# SwirlsV1_2.net
KiCad netlist of a schematic drawn in EAGLE
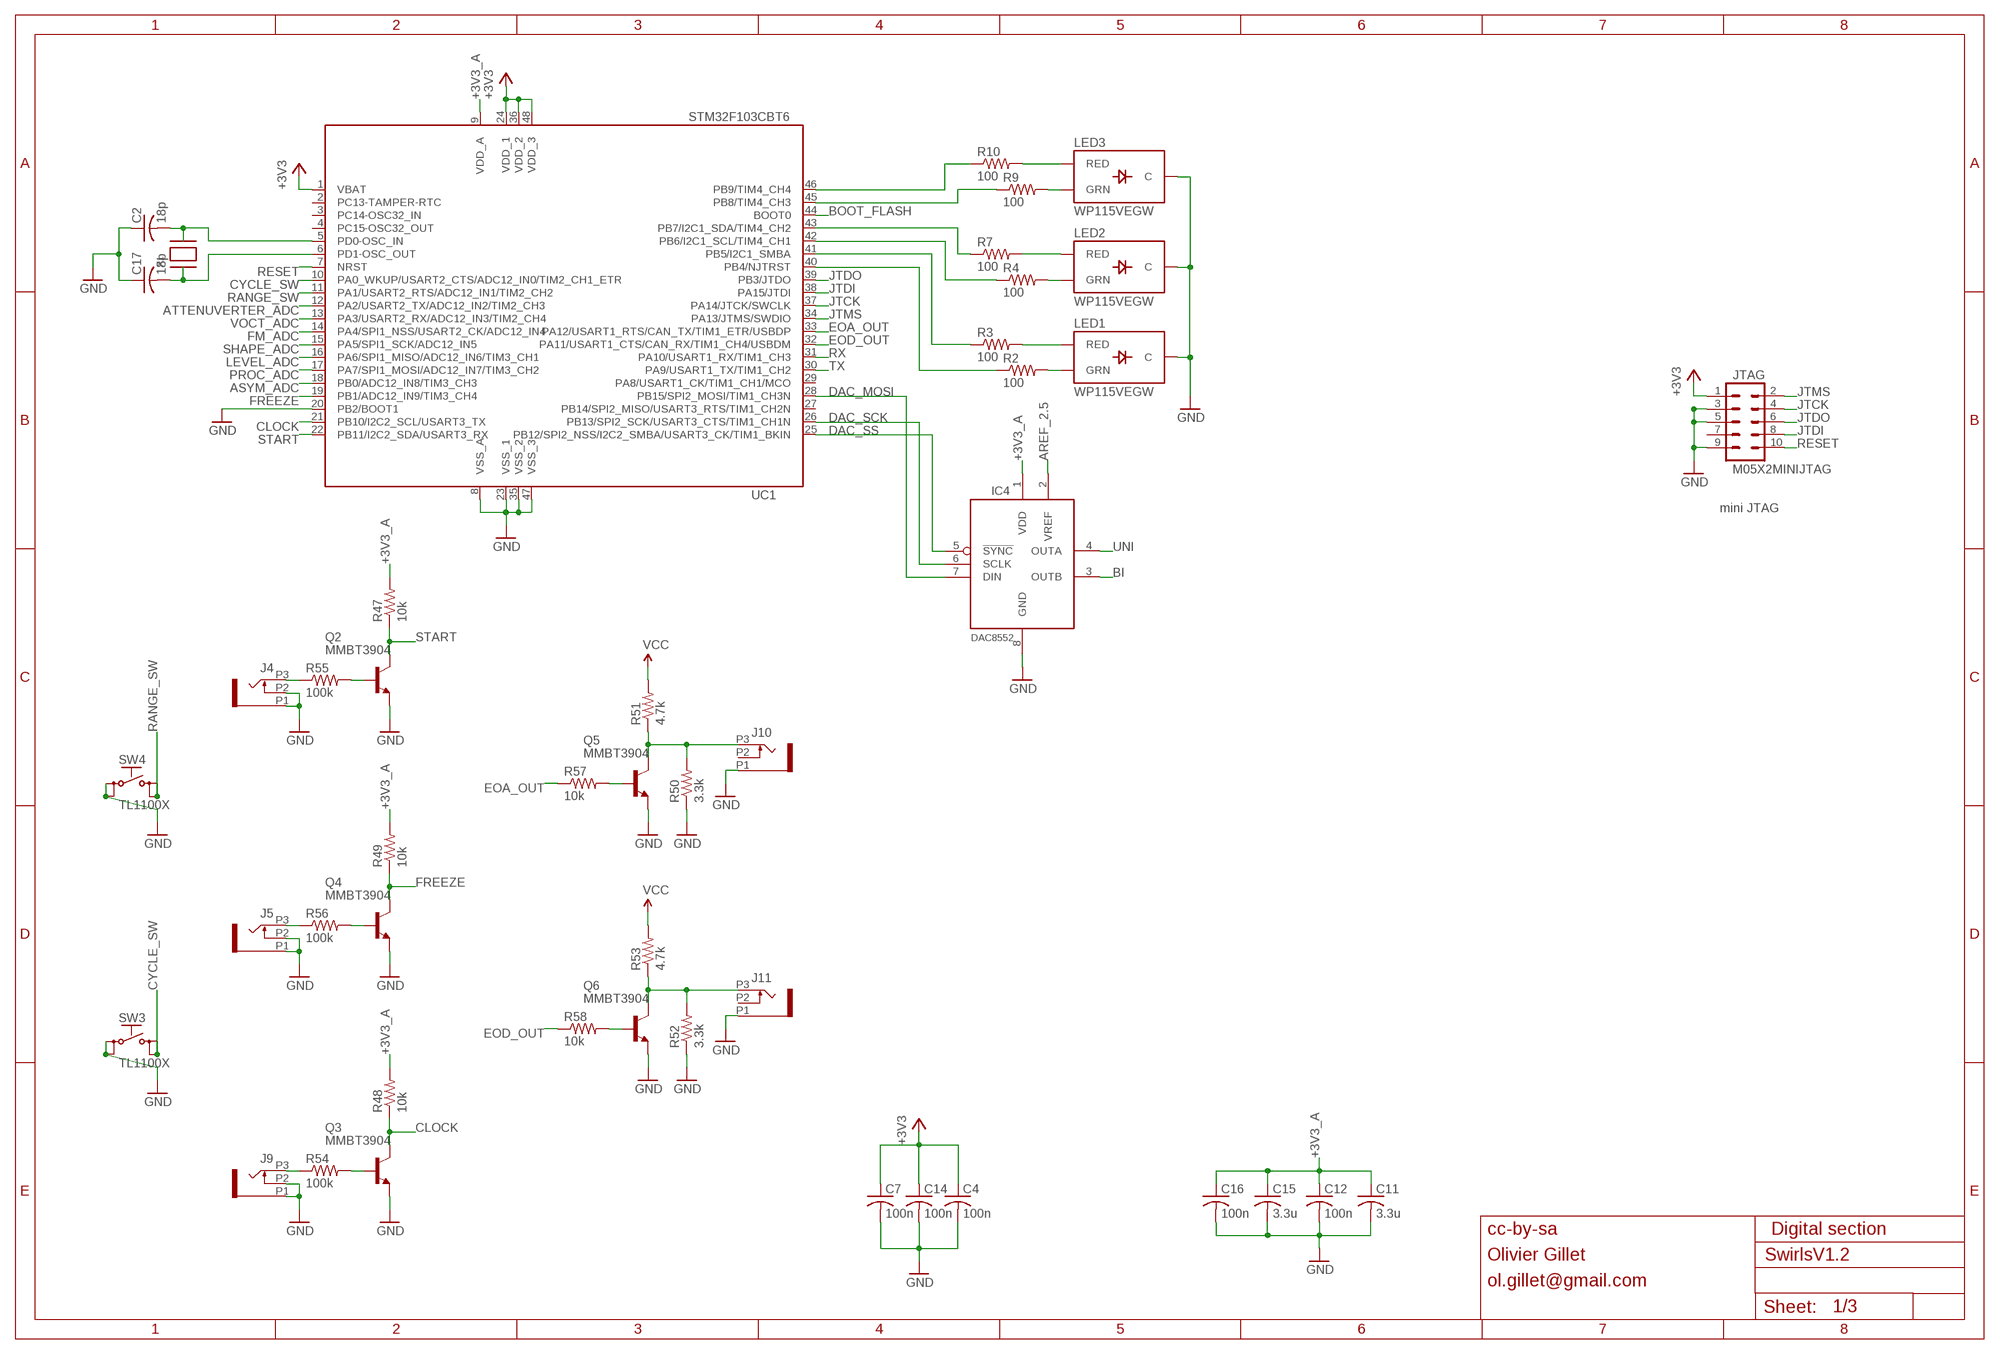
[diagram p0: schematic, sheet 1]
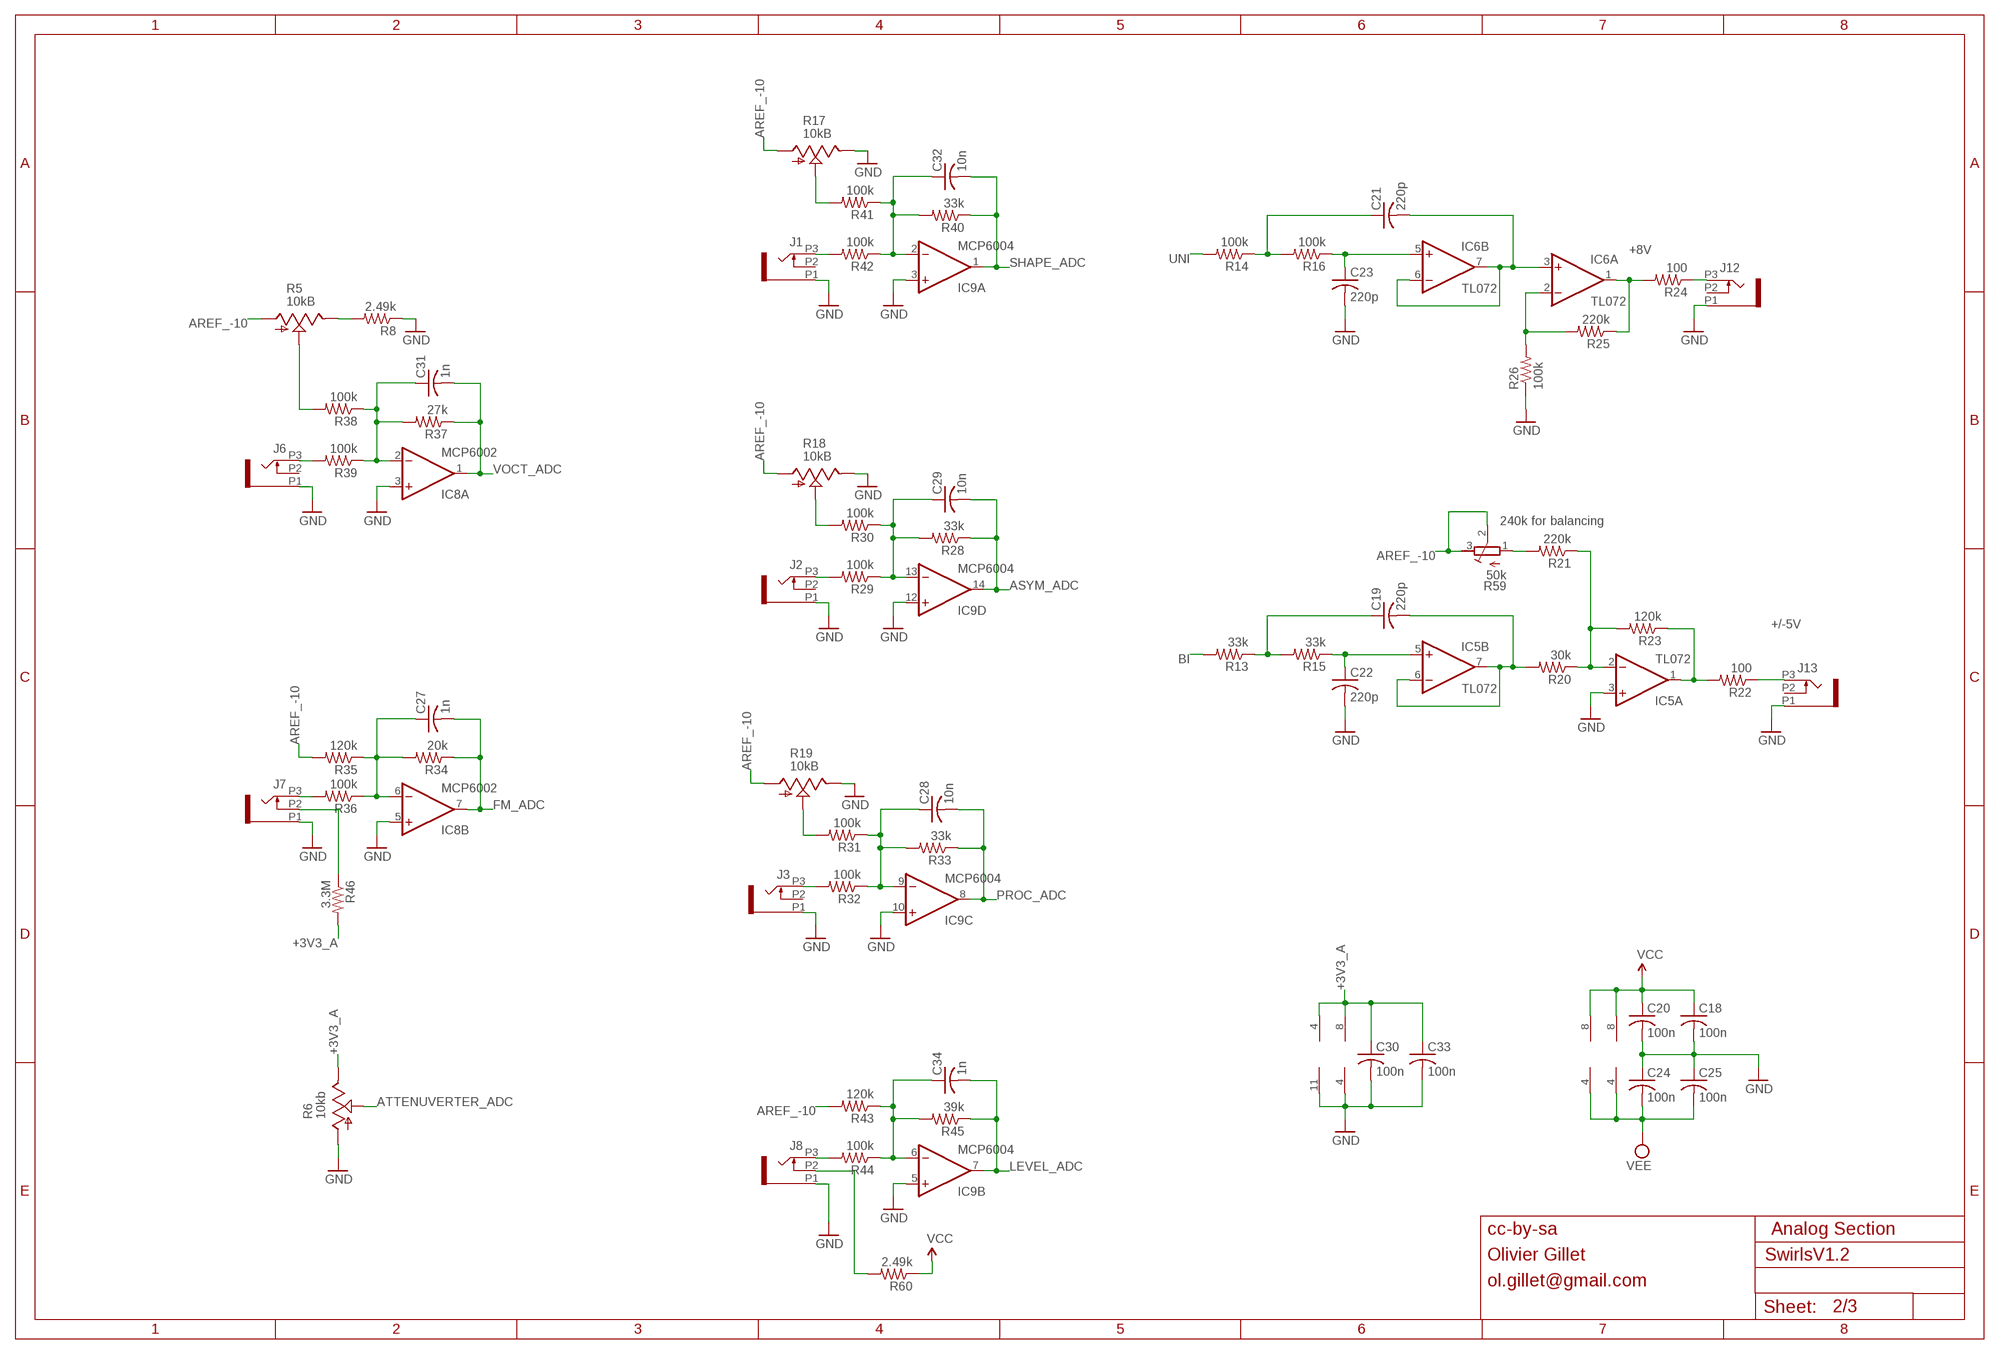
[diagram p1: schematic, sheet 2]
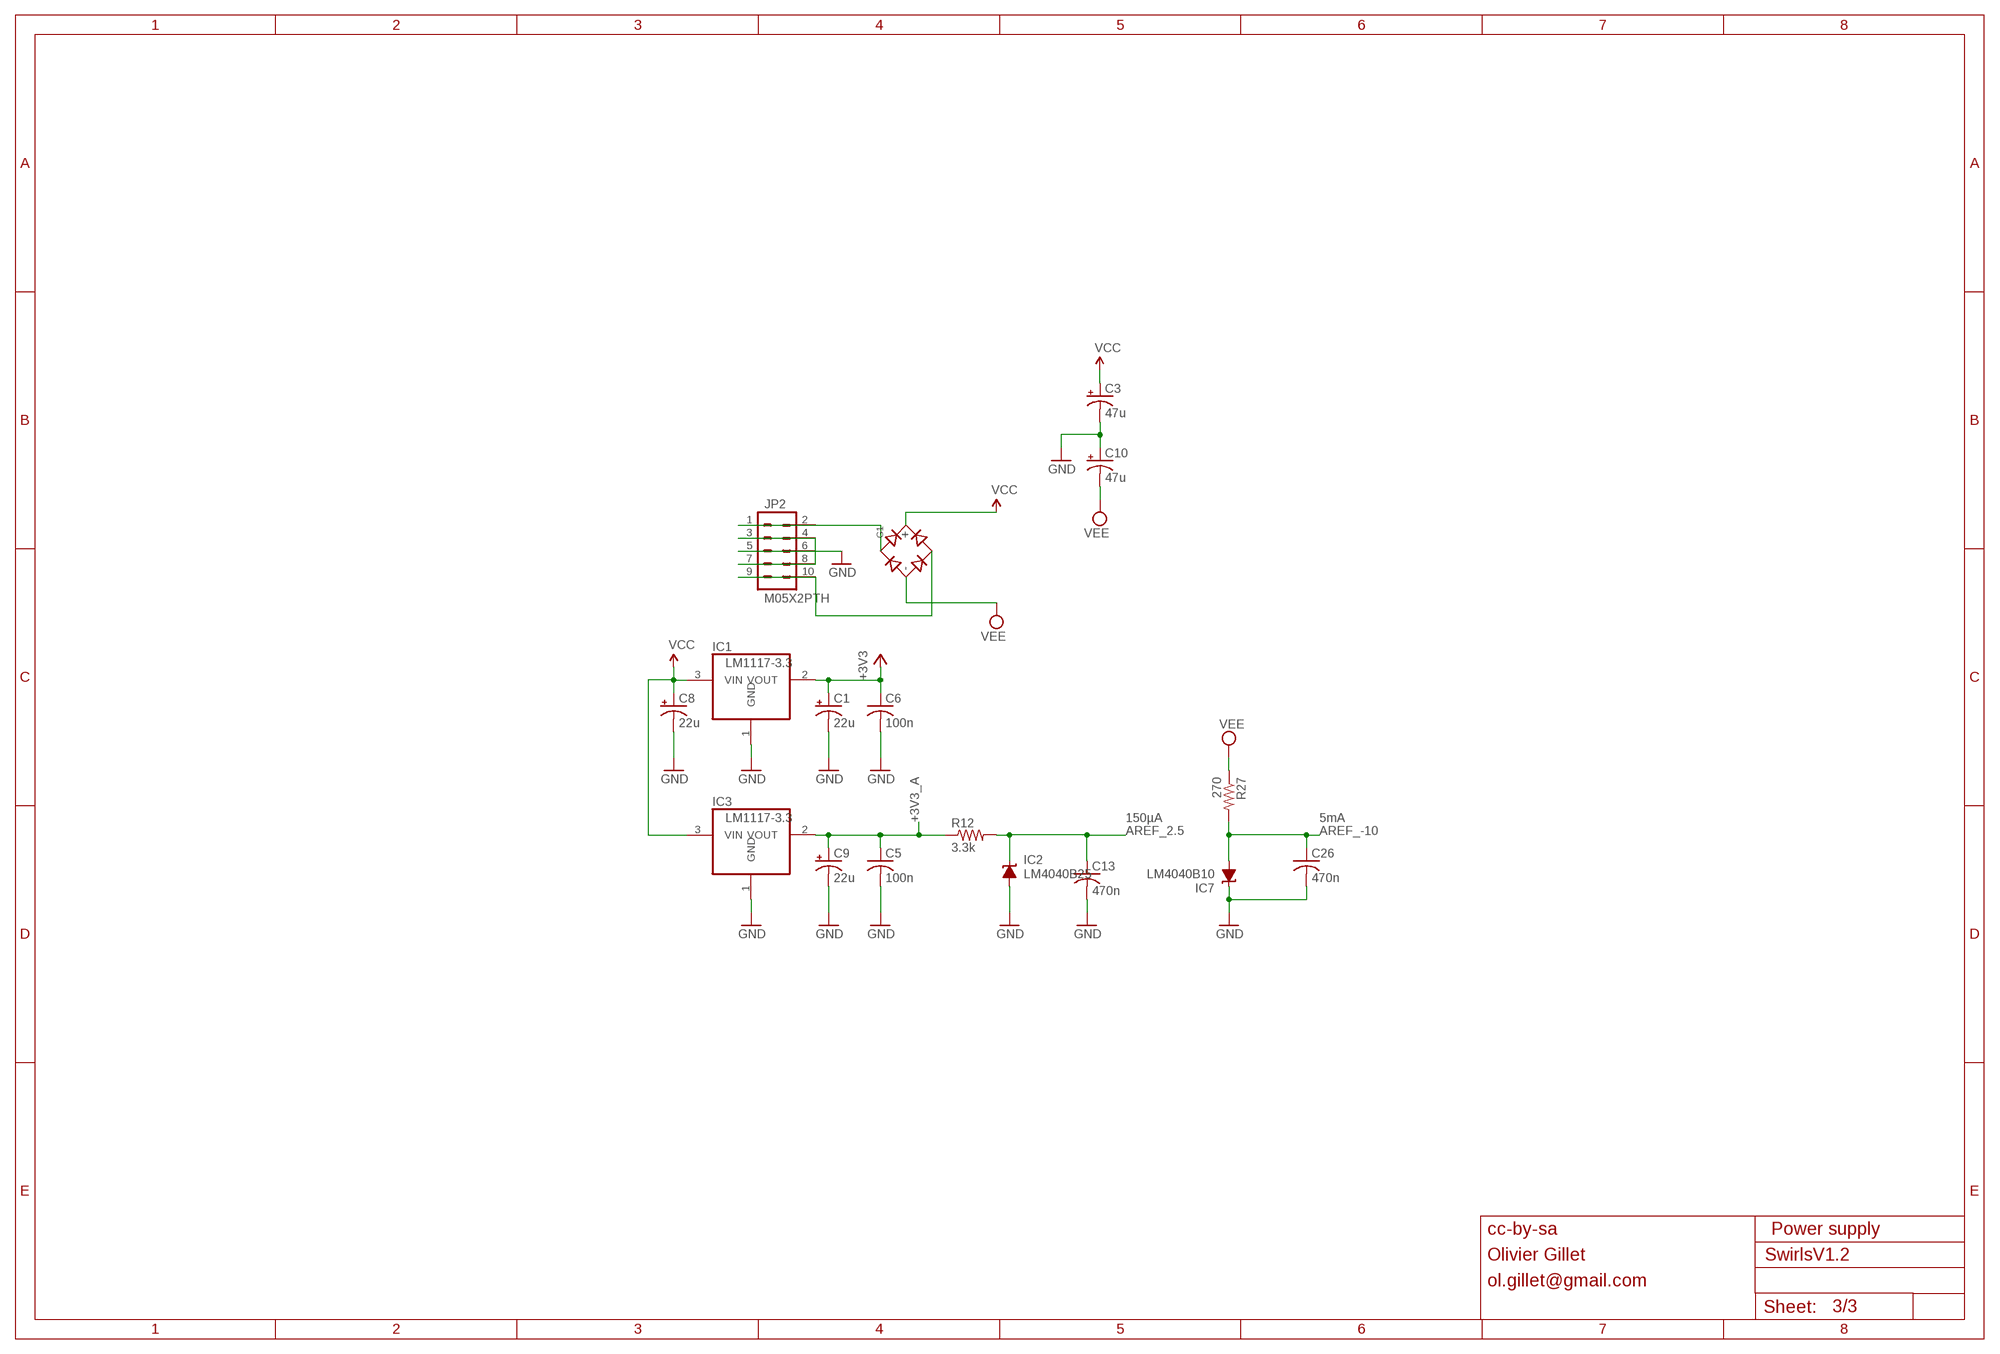
[diagram p2: schematic, sheet 3]

(export (version "E")
  (design (tool "Eeschema 10.0.6"))
  (components
    (comp (ref "C1")
      (value "22u")
      (footprint "eagle-import:PANASONIC_C")
      (libsource (lib "eagle-import") (part "CPOL-USC"))
    )
    (comp (ref "C3")
      (value "47u")
      (footprint "eagle-import:PANASONIC_C")
      (libsource (lib "eagle-import") (part "CPOL-USC"))
    )
    (comp (ref "C5")
      (value "100n")
      (footprint "eagle-import:C0603")
      (libsource (lib "eagle-import") (part "C-USC0603"))
    )
    (comp (ref "C6")
      (value "100n")
      (footprint "eagle-import:C0603")
      (libsource (lib "eagle-import") (part "C-USC0603"))
    )
    (comp (ref "C8")
      (value "22u")
      (footprint "eagle-import:PANASONIC_C")
      (libsource (lib "eagle-import") (part "CPOL-USC"))
    )
    (comp (ref "C9")
      (value "22u")
      (footprint "eagle-import:PANASONIC_C")
      (libsource (lib "eagle-import") (part "CPOL-USC"))
    )
    (comp (ref "C10")
      (value "47u")
      (footprint "eagle-import:PANASONIC_C")
      (libsource (lib "eagle-import") (part "CPOL-USC"))
    )
    (comp (ref "C13")
      (value "470n")
      (footprint "eagle-import:C0603")
      (libsource (lib "eagle-import") (part "C-USC0603"))
    )
    (comp (ref "C26")
      (value "470n")
      (footprint "eagle-import:C0603")
      (libsource (lib "eagle-import") (part "C-USC0603"))
    )
    (comp (ref "G1")
      (value "BRIDGERECTIFIER")
      (footprint "eagle-import:SOIC-4")
      (libsource (lib "eagle-import") (part "BRIDGERECTIFIER"))
    )
    (comp (ref "IC1")
      (value "LM1117-3.3")
      (footprint "eagle-import:SOT223")
      (libsource (lib "eagle-import") (part "REG1117"))
    )
    (comp (ref "IC2")
      (value "LM4040B25")
      (footprint "eagle-import:DBZ_R-PDSO-G3")
      (libsource (lib "eagle-import") (part "LM4041DBZB12"))
    )
    (comp (ref "IC3")
      (value "LM1117-3.3")
      (footprint "eagle-import:SOT223")
      (libsource (lib "eagle-import") (part "REG1117"))
    )
    (comp (ref "IC7")
      (value "LM4040B10")
      (footprint "eagle-import:DBZ_R-PDSO-G3")
      (libsource (lib "eagle-import") (part "LM4041DBZB12"))
    )
    (comp (ref "JP2")
      (value "M05X2PTH")
      (footprint "eagle-import:AVR_ICSP")
      (libsource (lib "eagle-import") (part "M05X2PTH"))
    )
    (comp (ref "R12")
      (value "3.3k")
      (footprint "eagle-import:R0603")
      (libsource (lib "eagle-import") (part "R-US_R0603"))
    )
    (comp (ref "R27")
      (value "270")
      (footprint "eagle-import:R0603")
      (libsource (lib "eagle-import") (part "R-US_R0603"))
    )
    (comp (ref "C2")
      (value "18p")
      (footprint "eagle-import:C0603")
      (libsource (lib "eagle-import") (part "C-USC0603"))
    )
    (comp (ref "C4")
      (value "100n")
      (footprint "eagle-import:C0603")
      (libsource (lib "eagle-import") (part "C-USC0603"))
    )
    (comp (ref "C7")
      (value "100n")
      (footprint "eagle-import:C0603")
      (libsource (lib "eagle-import") (part "C-USC0603"))
    )
    (comp (ref "C11")
      (value "3.3u")
      (footprint "eagle-import:C0603")
      (libsource (lib "eagle-import") (part "C-USC0603"))
    )
    (comp (ref "C12")
      (value "100n")
      (footprint "eagle-import:C0603")
      (libsource (lib "eagle-import") (part "C-USC0603"))
    )
    (comp (ref "C14")
      (value "100n")
      (footprint "eagle-import:C0603")
      (libsource (lib "eagle-import") (part "C-USC0603"))
    )
    (comp (ref "C15")
      (value "3.3u")
      (footprint "eagle-import:C0603")
      (libsource (lib "eagle-import") (part "C-USC0603"))
    )
    (comp (ref "C16")
      (value "100n")
      (footprint "eagle-import:C0603")
      (libsource (lib "eagle-import") (part "C-USC0603"))
    )
    (comp (ref "C17")
      (value "18p")
      (footprint "eagle-import:C0603")
      (libsource (lib "eagle-import") (part "C-USC0603"))
    )
    (comp (ref "IC4")
      (value "DAC8552")
      (footprint "eagle-import:MSOP-8")
      (libsource (lib "eagle-import") (part "DAC8552"))
    )
    (comp (ref "J4")
      (value "PJ301_GUI6")
      (footprint "eagle-import:OG-PJ301_VARIATIONS_WQP_PJ_301M6")
      (libsource (lib "eagle-import") (part "PJ301_GUI6"))
    )
    (comp (ref "J5")
      (value "PJ301_GUI6")
      (footprint "eagle-import:OG-PJ301_VARIATIONS_WQP_PJ_301M6")
      (libsource (lib "eagle-import") (part "PJ301_GUI6"))
    )
    (comp (ref "J9")
      (value "PJ301_GUI6")
      (footprint "eagle-import:OG-PJ301_VARIATIONS_WQP_PJ_301M6")
      (libsource (lib "eagle-import") (part "PJ301_GUI6"))
    )
    (comp (ref "J10")
      (value "PJ301_GUI6")
      (footprint "eagle-import:OG-PJ301_VARIATIONS_WQP_PJ_301M6")
      (libsource (lib "eagle-import") (part "PJ301_GUI6"))
    )
    (comp (ref "J11")
      (value "PJ301_GUI6")
      (footprint "eagle-import:OG-PJ301_VARIATIONS_WQP_PJ_301M6")
      (libsource (lib "eagle-import") (part "PJ301_GUI6"))
    )
    (comp (ref "JTAG")
      (value "M05X2MINIJTAG")
      (footprint "eagle-import:2X5-1.27")
      (libsource (lib "eagle-import") (part "og-header_M05X2MINIJTAG"))
    )
    (comp (ref "LED1")
      (value "WP115VEGW")
      (footprint "eagle-import:LED-BICOLOR-THROUGHHOLE")
      (libsource (lib "eagle-import") (part "LED-BICOLOR-THROUGHHOLE"))
    )
    (comp (ref "LED2")
      (value "WP115VEGW")
      (footprint "eagle-import:LED-BICOLOR-THROUGHHOLE")
      (libsource (lib "eagle-import") (part "LED-BICOLOR-THROUGHHOLE"))
    )
    (comp (ref "LED3")
      (value "WP115VEGW")
      (footprint "eagle-import:LED-BICOLOR-THROUGHHOLE")
      (libsource (lib "eagle-import") (part "LED-BICOLOR-THROUGHHOLE"))
    )
    (comp (ref "Q2")
      (value "MMBT3904")
      (footprint "eagle-import:SOT23-BEC")
      (libsource (lib "eagle-import") (part "-NPN-SOT23-BECMMBT3904LT1"))
    )
    (comp (ref "Q3")
      (value "MMBT3904")
      (footprint "eagle-import:SOT23-BEC")
      (libsource (lib "eagle-import") (part "-NPN-SOT23-BECMMBT3904LT1"))
    )
    (comp (ref "Q4")
      (value "MMBT3904")
      (footprint "eagle-import:SOT23-BEC")
      (libsource (lib "eagle-import") (part "-NPN-SOT23-BECMMBT3904LT1"))
    )
    (comp (ref "Q5")
      (value "MMBT3904")
      (footprint "eagle-import:SOT23-BEC")
      (libsource (lib "eagle-import") (part "-NPN-SOT23-BECMMBT3904LT1"))
    )
    (comp (ref "Q6")
      (value "MMBT3904")
      (footprint "eagle-import:SOT23-BEC")
      (libsource (lib "eagle-import") (part "-NPN-SOT23-BECMMBT3904LT1"))
    )
    (comp (ref "R2")
      (value "100")
      (footprint "eagle-import:R0603")
      (libsource (lib "eagle-import") (part "R-US_R0603"))
    )
    (comp (ref "R3")
      (value "100")
      (footprint "eagle-import:R0603")
      (libsource (lib "eagle-import") (part "R-US_R0603"))
    )
    (comp (ref "R4")
      (value "100")
      (footprint "eagle-import:R0603")
      (libsource (lib "eagle-import") (part "R-US_R0603"))
    )
    (comp (ref "R7")
      (value "100")
      (footprint "eagle-import:R0603")
      (libsource (lib "eagle-import") (part "R-US_R0603"))
    )
    (comp (ref "R9")
      (value "100")
      (footprint "eagle-import:R0603")
      (libsource (lib "eagle-import") (part "R-US_R0603"))
    )
    (comp (ref "R10")
      (value "100")
      (footprint "eagle-import:R0603")
      (libsource (lib "eagle-import") (part "R-US_R0603"))
    )
    (comp (ref "R47")
      (value "10k")
      (footprint "eagle-import:R0603")
      (libsource (lib "eagle-import") (part "R-US_R0603"))
    )
    (comp (ref "R48")
      (value "10k")
      (footprint "eagle-import:R0603")
      (libsource (lib "eagle-import") (part "R-US_R0603"))
    )
    (comp (ref "R49")
      (value "10k")
      (footprint "eagle-import:R0603")
      (libsource (lib "eagle-import") (part "R-US_R0603"))
    )
    (comp (ref "R50")
      (value "3.3k")
      (footprint "eagle-import:R0603")
      (libsource (lib "eagle-import") (part "R-US_R0603"))
    )
    (comp (ref "R51")
      (value "4.7k")
      (footprint "eagle-import:R0603")
      (libsource (lib "eagle-import") (part "R-US_R0603"))
    )
    (comp (ref "R52")
      (value "3.3k")
      (footprint "eagle-import:R0603")
      (libsource (lib "eagle-import") (part "R-US_R0603"))
    )
    (comp (ref "R53")
      (value "4.7k")
      (footprint "eagle-import:R0603")
      (libsource (lib "eagle-import") (part "R-US_R0603"))
    )
    (comp (ref "R54")
      (value "100k")
      (footprint "eagle-import:R0603")
      (libsource (lib "eagle-import") (part "R-US_R0603"))
    )
    (comp (ref "R55")
      (value "100k")
      (footprint "eagle-import:R0603")
      (libsource (lib "eagle-import") (part "R-US_R0603"))
    )
    (comp (ref "R56")
      (value "100k")
      (footprint "eagle-import:R0603")
      (libsource (lib "eagle-import") (part "R-US_R0603"))
    )
    (comp (ref "R57")
      (value "10k")
      (footprint "eagle-import:R0603")
      (libsource (lib "eagle-import") (part "R-US_R0603"))
    )
    (comp (ref "R58")
      (value "10k")
      (footprint "eagle-import:R0603")
      (libsource (lib "eagle-import") (part "R-US_R0603"))
    )
    (comp (ref "SW3")
      (value "TL1100X")
      (footprint "eagle-import:TL1100X")
      (libsource (lib "eagle-import") (part "TL1100X"))
    )
    (comp (ref "SW4")
      (value "TL1100X")
      (footprint "eagle-import:TL1100X")
      (libsource (lib "eagle-import") (part "TL1100X"))
    )
    (comp (ref "UC1")
      (value "STM32F103CBT6")
      (footprint "eagle-import:LQFP48")
      (libsource (lib "eagle-import") (part "STM32F103CB"))
    )
    (comp (ref "X1")
      (value "XTALNX5032")
      (footprint "eagle-import:NX5032")
      (libsource (lib "eagle-import") (part "XTALNX5032"))
    )
    (comp (ref "C18")
      (value "100n")
      (footprint "eagle-import:C0603")
      (libsource (lib "eagle-import") (part "C-USC0603"))
    )
    (comp (ref "C19")
      (value "220p")
      (footprint "eagle-import:C0603")
      (libsource (lib "eagle-import") (part "C-USC0603"))
    )
    (comp (ref "C20")
      (value "100n")
      (footprint "eagle-import:C0603")
      (libsource (lib "eagle-import") (part "C-USC0603"))
    )
    (comp (ref "C21")
      (value "220p")
      (footprint "eagle-import:C0603")
      (libsource (lib "eagle-import") (part "C-USC0603"))
    )
    (comp (ref "C22")
      (value "220p")
      (footprint "eagle-import:C0603")
      (libsource (lib "eagle-import") (part "C-USC0603"))
    )
    (comp (ref "C23")
      (value "220p")
      (footprint "eagle-import:C0603")
      (libsource (lib "eagle-import") (part "C-USC0603"))
    )
    (comp (ref "C24")
      (value "100n")
      (footprint "eagle-import:C0603")
      (libsource (lib "eagle-import") (part "C-USC0603"))
    )
    (comp (ref "C25")
      (value "100n")
      (footprint "eagle-import:C0603")
      (libsource (lib "eagle-import") (part "C-USC0603"))
    )
    (comp (ref "C27")
      (value "1n")
      (footprint "eagle-import:C0603")
      (libsource (lib "eagle-import") (part "C-USC0603"))
    )
    (comp (ref "C28")
      (value "10n")
      (footprint "eagle-import:C0603")
      (libsource (lib "eagle-import") (part "C-USC0603"))
    )
    (comp (ref "C29")
      (value "10n")
      (footprint "eagle-import:C0603")
      (libsource (lib "eagle-import") (part "C-USC0603"))
    )
    (comp (ref "C30")
      (value "100n")
      (footprint "eagle-import:C0603")
      (libsource (lib "eagle-import") (part "C-USC0603"))
    )
    (comp (ref "C31")
      (value "1n")
      (footprint "eagle-import:C0603")
      (libsource (lib "eagle-import") (part "C-USC0603"))
    )
    (comp (ref "C32")
      (value "10n")
      (footprint "eagle-import:C0603")
      (libsource (lib "eagle-import") (part "C-USC0603"))
    )
    (comp (ref "C33")
      (value "100n")
      (footprint "eagle-import:C0603")
      (libsource (lib "eagle-import") (part "C-USC0603"))
    )
    (comp (ref "C34")
      (value "1n")
      (footprint "eagle-import:C0603")
      (libsource (lib "eagle-import") (part "C-USC0603"))
    )
    (comp (ref "IC5")
      (value "TL072")
      (footprint "eagle-import:TSSOP-8")
      (libsource (lib "eagle-import") (part "TL072TSSOP"))
    )
    (comp (ref "IC6")
      (value "TL072")
      (footprint "eagle-import:TSSOP-8")
      (libsource (lib "eagle-import") (part "TL072TSSOP"))
    )
    (comp (ref "IC8")
      (value "MCP6002")
      (footprint "eagle-import:SO08")
      (libsource (lib "eagle-import") (part "TL072D"))
    )
    (comp (ref "IC9")
      (value "MCP6004")
      (footprint "eagle-import:TSSOP14")
      (libsource (lib "eagle-import") (part "MCP6004ST"))
    )
    (comp (ref "J1")
      (value "PJ301_GUI6")
      (footprint "eagle-import:OG-PJ301_VARIATIONS_WQP_PJ_301M6")
      (libsource (lib "eagle-import") (part "PJ301_GUI6"))
    )
    (comp (ref "J2")
      (value "PJ301_GUI6")
      (footprint "eagle-import:OG-PJ301_VARIATIONS_WQP_PJ_301M6")
      (libsource (lib "eagle-import") (part "PJ301_GUI6"))
    )
    (comp (ref "J3")
      (value "PJ301_GUI6")
      (footprint "eagle-import:OG-PJ301_VARIATIONS_WQP_PJ_301M6")
      (libsource (lib "eagle-import") (part "PJ301_GUI6"))
    )
    (comp (ref "J6")
      (value "PJ301_GUI6")
      (footprint "eagle-import:OG-PJ301_VARIATIONS_WQP_PJ_301M6")
      (libsource (lib "eagle-import") (part "PJ301_GUI6"))
    )
    (comp (ref "J7")
      (value "PJ301_GUI6")
      (footprint "eagle-import:OG-PJ301_VARIATIONS_WQP_PJ_301M6")
      (libsource (lib "eagle-import") (part "PJ301_GUI6"))
    )
    (comp (ref "J8")
      (value "PJ301_GUI6")
      (footprint "eagle-import:OG-PJ301_VARIATIONS_WQP_PJ_301M6")
      (libsource (lib "eagle-import") (part "PJ301_GUI6"))
    )
    (comp (ref "J12")
      (value "PJ301_GUI6")
      (footprint "eagle-import:OG-PJ301_VARIATIONS_WQP_PJ_301M6")
      (libsource (lib "eagle-import") (part "PJ301_GUI6"))
    )
    (comp (ref "J13")
      (value "PJ301_GUI6")
      (footprint "eagle-import:OG-PJ301_VARIATIONS_WQP_PJ_301M6")
      (libsource (lib "eagle-import") (part "PJ301_GUI6"))
    )
    (comp (ref "R5")
      (value "10kB")
      (footprint "eagle-import:ALPS_POT_VERTICAL_PS")
      (libsource (lib "eagle-import") (part "POT_USVERTICAL_PS"))
    )
    (comp (ref "R6")
      (value "10kb")
      (footprint "eagle-import:TALLTRIMMER")
      (libsource (lib "eagle-import") (part "POT-ALPS_POT_US"))
    )
    (comp (ref "R8")
      (value "2.49k")
      (footprint "eagle-import:R0603")
      (libsource (lib "eagle-import") (part "R-US_R0603"))
    )
    (comp (ref "R13")
      (value "33k")
      (footprint "eagle-import:R0603")
      (libsource (lib "eagle-import") (part "R-US_R0603"))
    )
    (comp (ref "R14")
      (value "100k")
      (footprint "eagle-import:R0603")
      (libsource (lib "eagle-import") (part "R-US_R0603"))
    )
    (comp (ref "R15")
      (value "33k")
      (footprint "eagle-import:R0603")
      (libsource (lib "eagle-import") (part "R-US_R0603"))
    )
    (comp (ref "R16")
      (value "100k")
      (footprint "eagle-import:R0603")
      (libsource (lib "eagle-import") (part "R-US_R0603"))
    )
    (comp (ref "R17")
      (value "10kB")
      (footprint "eagle-import:TALLTRIMMER")
      (libsource (lib "eagle-import") (part "POT-ALPS_POT_US"))
    )
    (comp (ref "R18")
      (value "10kB")
      (footprint "eagle-import:TALLTRIMMER")
      (libsource (lib "eagle-import") (part "POT-ALPS_POT_US"))
    )
    (comp (ref "R19")
      (value "10kB")
      (footprint "eagle-import:TALLTRIMMER")
      (libsource (lib "eagle-import") (part "POT-ALPS_POT_US"))
    )
    (comp (ref "R20")
      (value "30k")
      (footprint "eagle-import:R0603")
      (libsource (lib "eagle-import") (part "R-US_R0603"))
    )
    (comp (ref "R21")
      (value "220k")
      (footprint "eagle-import:R0603")
      (libsource (lib "eagle-import") (part "R-US_R0603"))
    )
    (comp (ref "R22")
      (value "100")
      (footprint "eagle-import:R0603")
      (libsource (lib "eagle-import") (part "R-US_R0603"))
    )
    (comp (ref "R23")
      (value "120k")
      (footprint "eagle-import:R0603")
      (libsource (lib "eagle-import") (part "R-US_R0603"))
    )
    (comp (ref "R24")
      (value "100")
      (footprint "eagle-import:R0603")
      (libsource (lib "eagle-import") (part "R-US_R0603"))
    )
    (comp (ref "R25")
      (value "220k")
      (footprint "eagle-import:R0603")
      (libsource (lib "eagle-import") (part "R-US_R0603"))
    )
    (comp (ref "R26")
      (value "100k")
      (footprint "eagle-import:R0603")
      (libsource (lib "eagle-import") (part "R-US_R0603"))
    )
    (comp (ref "R28")
      (value "33k")
      (footprint "eagle-import:R0603")
      (libsource (lib "eagle-import") (part "R-US_R0603"))
    )
    (comp (ref "R29")
      (value "100k")
      (footprint "eagle-import:R0603")
      (libsource (lib "eagle-import") (part "R-US_R0603"))
    )
    (comp (ref "R30")
      (value "100k")
      (footprint "eagle-import:R0603")
      (libsource (lib "eagle-import") (part "R-US_R0603"))
    )
    (comp (ref "R31")
      (value "100k")
      (footprint "eagle-import:R0603")
      (libsource (lib "eagle-import") (part "R-US_R0603"))
    )
    (comp (ref "R32")
      (value "100k")
      (footprint "eagle-import:R0603")
      (libsource (lib "eagle-import") (part "R-US_R0603"))
    )
    (comp (ref "R33")
      (value "33k")
      (footprint "eagle-import:R0603")
      (libsource (lib "eagle-import") (part "R-US_R0603"))
    )
    (comp (ref "R34")
      (value "20k")
      (footprint "eagle-import:R0603")
      (libsource (lib "eagle-import") (part "R-US_R0603"))
    )
    (comp (ref "R35")
      (value "120k")
      (footprint "eagle-import:R0603")
      (libsource (lib "eagle-import") (part "R-US_R0603"))
    )
    (comp (ref "R36")
      (value "100k")
      (footprint "eagle-import:R0603")
      (libsource (lib "eagle-import") (part "R-US_R0603"))
    )
    (comp (ref "R37")
      (value "27k")
      (footprint "eagle-import:R0603")
      (libsource (lib "eagle-import") (part "R-US_R0603"))
    )
    (comp (ref "R38")
      (value "100k")
      (footprint "eagle-import:R0603")
      (libsource (lib "eagle-import") (part "R-US_R0603"))
    )
    (comp (ref "R39")
      (value "100k")
      (footprint "eagle-import:R0603")
      (libsource (lib "eagle-import") (part "R-US_R0603"))
    )
    (comp (ref "R40")
      (value "33k")
      (footprint "eagle-import:R0603")
      (libsource (lib "eagle-import") (part "R-US_R0603"))
    )
    (comp (ref "R41")
      (value "100k")
      (footprint "eagle-import:R0603")
      (libsource (lib "eagle-import") (part "R-US_R0603"))
    )
    (comp (ref "R42")
      (value "100k")
      (footprint "eagle-import:R0603")
      (libsource (lib "eagle-import") (part "R-US_R0603"))
    )
    (comp (ref "R43")
      (value "120k")
      (footprint "eagle-import:R0603")
      (libsource (lib "eagle-import") (part "R-US_R0603"))
    )
    (comp (ref "R44")
      (value "100k")
      (footprint "eagle-import:R0603")
      (libsource (lib "eagle-import") (part "R-US_R0603"))
    )
    (comp (ref "R45")
      (value "39k")
      (footprint "eagle-import:R0603")
      (libsource (lib "eagle-import") (part "R-US_R0603"))
    )
    (comp (ref "R46")
      (value "3.3M")
      (footprint "eagle-import:R0603")
      (libsource (lib "eagle-import") (part "R-US_R0603"))
    )
    (comp (ref "R59")
      (value "50k")
      (footprint "eagle-import:RTRIM3296W")
      (libsource (lib "eagle-import") (part "R-TRIMM3296W"))
    )
    (comp (ref "R60")
      (value "2.49k")
      (footprint "eagle-import:R0805")
      (libsource (lib "eagle-import") (part "R-US_R0805"))
    )
  )
  (nets
    (net (code "1") (name "+3V3") (class "Default")
      (node (ref "C1") (pin "+") (pinfunction "+_+") (pintype "passive"))
      (node (ref "C14") (pin "1") (pinfunction "1_1") (pintype "passive"))
      (node (ref "C4") (pin "1") (pinfunction "1_1") (pintype "passive"))
      (node (ref "C6") (pin "1") (pinfunction "1_1") (pintype "passive"))
      (node (ref "C7") (pin "1") (pinfunction "1_1") (pintype "passive"))
      (node (ref "IC1") (pin "2") (pinfunction "VOUT_2") (pintype "output"))
      (node (ref "JTAG") (pin "1") (pinfunction "1_1") (pintype "passive"))
      (node (ref "UC1") (pin "1") (pinfunction "VBAT_1") (pintype "power_in"))
      (node (ref "UC1") (pin "24") (pinfunction "VDD_1_24") (pintype "power_in"))
      (node (ref "UC1") (pin "36") (pinfunction "VDD_2_36") (pintype "power_in"))
      (node (ref "UC1") (pin "48") (pinfunction "VDD_3_48") (pintype "power_in"))
    )
    (net (code "2") (name "+3V3_A") (class "Default")
      (node (ref "C11") (pin "1") (pinfunction "1_1") (pintype "passive"))
      (node (ref "C12") (pin "1") (pinfunction "1_1") (pintype "passive"))
      (node (ref "C15") (pin "1") (pinfunction "1_1") (pintype "passive"))
      (node (ref "C16") (pin "1") (pinfunction "1_1") (pintype "passive"))
      (node (ref "C30") (pin "1") (pinfunction "1_1") (pintype "passive"))
      (node (ref "C33") (pin "1") (pinfunction "1_1") (pintype "passive"))
      (node (ref "C5") (pin "1") (pinfunction "1_1") (pintype "passive"))
      (node (ref "C9") (pin "+") (pinfunction "+_+") (pintype "passive"))
      (node (ref "IC3") (pin "2") (pinfunction "VOUT_2") (pintype "output"))
      (node (ref "IC4") (pin "1") (pinfunction "VDD_1") (pintype "power_in"))
      (node (ref "IC8") (pin "8") (pinfunction "V+_8") (pintype "power_in"))
      (node (ref "IC9") (pin "4") (pinfunction "V+_4") (pintype "power_in"))
      (node (ref "R12") (pin "1") (pinfunction "1_1") (pintype "passive"))
      (node (ref "R46") (pin "2") (pinfunction "2_2") (pintype "passive"))
      (node (ref "R47") (pin "2") (pinfunction "2_2") (pintype "passive"))
      (node (ref "R48") (pin "2") (pinfunction "2_2") (pintype "passive"))
      (node (ref "R49") (pin "2") (pinfunction "2_2") (pintype "passive"))
      (node (ref "R6") (pin "P$1") (pinfunction "E_P$1") (pintype "passive"))
      (node (ref "UC1") (pin "9") (pinfunction "VDD_A_9") (pintype "power_in"))
    )
    (net (code "3") (name "AREF_-10") (class "Default")
      (node (ref "C26") (pin "1") (pinfunction "1_1") (pintype "passive"))
      (node (ref "IC7") (pin "2") (pinfunction "A_2") (pintype "passive"))
      (node (ref "R17") (pin "P$3") (pinfunction "A_P$3") (pintype "passive"))
      (node (ref "R18") (pin "P$3") (pinfunction "A_P$3") (pintype "passive"))
      (node (ref "R19") (pin "P$3") (pinfunction "A_P$3") (pintype "passive"))
      (node (ref "R27") (pin "2") (pinfunction "2_2") (pintype "passive"))
      (node (ref "R35") (pin "2") (pinfunction "2_2") (pintype "passive"))
      (node (ref "R43") (pin "2") (pinfunction "2_2") (pintype "passive"))
      (node (ref "R5") (pin "P$3") (pinfunction "A_P$3") (pintype "passive"))
      (node (ref "R59") (pin "2") (pinfunction "S_2") (pintype "passive"))
      (node (ref "R59") (pin "3") (pinfunction "E_3") (pintype "passive"))
    )
    (net (code "4") (name "AREF_2.5") (class "Default")
      (node (ref "C13") (pin "1") (pinfunction "1_1") (pintype "passive"))
      (node (ref "IC2") (pin "1") (pinfunction "C_1") (pintype "passive"))
      (node (ref "IC4") (pin "2") (pinfunction "VREF_2") (pintype "power_in"))
      (node (ref "R12") (pin "2") (pinfunction "2_2") (pintype "passive"))
    )
    (net (code "5") (name "ASYM_ADC") (class "Default")
      (node (ref "C29") (pin "2") (pinfunction "2_2") (pintype "passive"))
      (node (ref "IC9") (pin "14") (pinfunction "OUT_14") (pintype "output"))
      (node (ref "R28") (pin "1") (pinfunction "1_1") (pintype "passive"))
      (node (ref "UC1") (pin "18") (pinfunction "PB0/ADC12_IN8/TIM3_CH3_18") (pintype "bidirectional"))
    )
    (net (code "6") (name "ATTENUVERTER_ADC") (class "Default")
      (node (ref "R6") (pin "P$2") (pinfunction "S_P$2") (pintype "passive"))
      (node (ref "UC1") (pin "12") (pinfunction "PA2/USART2_TX/ADC12_IN2/TIM2_CH3_12") (pintype "bidirectional"))
    )
    (net (code "7") (name "BI") (class "Default")
      (node (ref "IC4") (pin "3") (pinfunction "OUTB_3") (pintype "input"))
      (node (ref "R13") (pin "2") (pinfunction "2_2") (pintype "passive"))
    )
    (net (code "8") (name "BOOT_FLASH") (class "Default")
      (node (ref "UC1") (pin "44") (pinfunction "BOOT0_44") (pintype "input"))
    )
    (net (code "9") (name "CLOCK") (class "Default")
      (node (ref "Q3") (pin "C") (pinfunction "C_C") (pintype "passive"))
      (node (ref "R48") (pin "1") (pinfunction "1_1") (pintype "passive"))
      (node (ref "UC1") (pin "21") (pinfunction "PB10/I2C2_SCL/USART3_TX_21") (pintype "input"))
    )
    (net (code "10") (name "CYCLE_SW") (class "Default")
      (node (ref "SW3") (pin "3") (pinfunction "S_3") (pintype "passive"))
      (node (ref "SW3") (pin "4") (pinfunction "S1_4") (pintype "passive"))
      (node (ref "UC1") (pin "10") (pinfunction "PA0_WKUP/USART2_CTS/ADC12_IN0/TIM2_CH1_ETR_10") (pintype "bidirectional"))
    )
    (net (code "11") (name "DAC_MOSI") (class "Default")
      (node (ref "IC4") (pin "7") (pinfunction "DIN_7") (pintype "bidirectional"))
      (node (ref "UC1") (pin "28") (pinfunction "PB15/SPI2_MOSI/TIM1_CH3N_28") (pintype "input"))
    )
    (net (code "12") (name "DAC_SCK") (class "Default")
      (node (ref "IC4") (pin "6") (pinfunction "SCLK_6") (pintype "bidirectional"))
      (node (ref "UC1") (pin "26") (pinfunction "PB13/SPI2_SCK/USART3_CTS/TIM1_CH1N_26") (pintype "input"))
    )
    (net (code "13") (name "DAC_SS") (class "Default")
      (node (ref "IC4") (pin "5") (pinfunction "~{SYNC}_5") (pintype "bidirectional"))
      (node (ref "UC1") (pin "25") (pinfunction "PB12/SPI2_NSS/I2C2_SMBA/USART3_CK/TIM1_BKIN_25") (pintype "input"))
    )
    (net (code "14") (name "EOA_OUT") (class "Default")
      (node (ref "R57") (pin "1") (pinfunction "1_1") (pintype "passive"))
      (node (ref "UC1") (pin "33") (pinfunction "PA12/USART1_RTS/CAN_TX/TIM1_ETR/USBDP_33") (pintype "bidirectional"))
    )
    (net (code "15") (name "EOD_OUT") (class "Default")
      (node (ref "R58") (pin "1") (pinfunction "1_1") (pintype "passive"))
      (node (ref "UC1") (pin "32") (pinfunction "PA11/USART1_CTS/CAN_RX/TIM1_CH4/USBDM_32") (pintype "bidirectional"))
    )
    (net (code "16") (name "FM_ADC") (class "Default")
      (node (ref "C27") (pin "2") (pinfunction "2_2") (pintype "passive"))
      (node (ref "IC8") (pin "7") (pinfunction "OUT_7") (pintype "output"))
      (node (ref "R34") (pin "1") (pinfunction "1_1") (pintype "passive"))
      (node (ref "UC1") (pin "14") (pinfunction "PA4/SPI1_NSS/USART2_CK/ADC12_IN4_14") (pintype "bidirectional"))
    )
    (net (code "17") (name "FREEZE") (class "Default")
      (node (ref "Q4") (pin "C") (pinfunction "C_C") (pintype "passive"))
      (node (ref "R49") (pin "1") (pinfunction "1_1") (pintype "passive"))
      (node (ref "UC1") (pin "19") (pinfunction "PB1/ADC12_IN9/TIM3_CH4_19") (pintype "bidirectional"))
    )
    (net (code "18") (name "GND") (class "Default")
      (node (ref "C1") (pin "-") (pinfunction "-_-") (pintype "passive"))
      (node (ref "C10") (pin "+") (pinfunction "+_+") (pintype "passive"))
      (node (ref "C11") (pin "2") (pinfunction "2_2") (pintype "passive"))
      (node (ref "C12") (pin "2") (pinfunction "2_2") (pintype "passive"))
      (node (ref "C13") (pin "2") (pinfunction "2_2") (pintype "passive"))
      (node (ref "C14") (pin "2") (pinfunction "2_2") (pintype "passive"))
      (node (ref "C15") (pin "2") (pinfunction "2_2") (pintype "passive"))
      (node (ref "C16") (pin "2") (pinfunction "2_2") (pintype "passive"))
      (node (ref "C17") (pin "1") (pinfunction "1_1") (pintype "passive"))
      (node (ref "C18") (pin "2") (pinfunction "2_2") (pintype "passive"))
      (node (ref "C2") (pin "1") (pinfunction "1_1") (pintype "passive"))
      (node (ref "C20") (pin "2") (pinfunction "2_2") (pintype "passive"))
      (node (ref "C22") (pin "2") (pinfunction "2_2") (pintype "passive"))
      (node (ref "C23") (pin "2") (pinfunction "2_2") (pintype "passive"))
      (node (ref "C24") (pin "1") (pinfunction "1_1") (pintype "passive"))
      (node (ref "C25") (pin "1") (pinfunction "1_1") (pintype "passive"))
      (node (ref "C26") (pin "2") (pinfunction "2_2") (pintype "passive"))
      (node (ref "C3") (pin "-") (pinfunction "-_-") (pintype "passive"))
      (node (ref "C30") (pin "2") (pinfunction "2_2") (pintype "passive"))
      (node (ref "C33") (pin "2") (pinfunction "2_2") (pintype "passive"))
      (node (ref "C4") (pin "2") (pinfunction "2_2") (pintype "passive"))
      (node (ref "C5") (pin "2") (pinfunction "2_2") (pintype "passive"))
      (node (ref "C6") (pin "2") (pinfunction "2_2") (pintype "passive"))
      (node (ref "C7") (pin "2") (pinfunction "2_2") (pintype "passive"))
      (node (ref "C8") (pin "-") (pinfunction "-_-") (pintype "passive"))
      (node (ref "C9") (pin "-") (pinfunction "-_-") (pintype "passive"))
      (node (ref "IC1") (pin "1") (pinfunction "GND_1") (pintype "power_in"))
      (node (ref "IC2") (pin "2") (pinfunction "A_2") (pintype "passive"))
      (node (ref "IC3") (pin "1") (pinfunction "GND_1") (pintype "power_in"))
      (node (ref "IC4") (pin "8") (pinfunction "GND_8") (pintype "power_in"))
      (node (ref "IC5") (pin "3") (pinfunction "+IN_3") (pintype "input"))
      (node (ref "IC7") (pin "1") (pinfunction "C_1") (pintype "passive"))
      (node (ref "IC8") (pin "3") (pinfunction "+IN_3") (pintype "input"))
      (node (ref "IC8") (pin "4") (pinfunction "V-_4") (pintype "power_in"))
      (node (ref "IC8") (pin "5") (pinfunction "+IN_5") (pintype "input"))
      (node (ref "IC9") (pin "10") (pinfunction "+IN_10") (pintype "input"))
      (node (ref "IC9") (pin "11") (pinfunction "V-_11") (pintype "power_in"))
      (node (ref "IC9") (pin "12") (pinfunction "+IN_12") (pintype "input"))
      (node (ref "IC9") (pin "3") (pinfunction "+IN_3") (pintype "input"))
      (node (ref "IC9") (pin "5") (pinfunction "+IN_5") (pintype "input"))
      (node (ref "J1") (pin "P1") (pinfunction "1_P1") (pintype "passive"))
      (node (ref "J10") (pin "P1") (pinfunction "1_P1") (pintype "passive"))
      (node (ref "J11") (pin "P1") (pinfunction "1_P1") (pintype "passive"))
      (node (ref "J12") (pin "P1") (pinfunction "1_P1") (pintype "passive"))
      (node (ref "J13") (pin "P1") (pinfunction "1_P1") (pintype "passive"))
      (node (ref "J2") (pin "P1") (pinfunction "1_P1") (pintype "passive"))
      (node (ref "J3") (pin "P1") (pinfunction "1_P1") (pintype "passive"))
      (node (ref "J4") (pin "P1") (pinfunction "1_P1") (pintype "passive"))
      (node (ref "J4") (pin "P2") (pinfunction "2_P2") (pintype "passive"))
      (node (ref "J5") (pin "P1") (pinfunction "1_P1") (pintype "passive"))
      (node (ref "J5") (pin "P2") (pinfunction "2_P2") (pintype "passive"))
      (node (ref "J6") (pin "P1") (pinfunction "1_P1") (pintype "passive"))
      (node (ref "J7") (pin "P1") (pinfunction "1_P1") (pintype "passive"))
      (node (ref "J8") (pin "P1") (pinfunction "1_P1") (pintype "passive"))
      (node (ref "J9") (pin "P1") (pinfunction "1_P1") (pintype "passive"))
      (node (ref "J9") (pin "P2") (pinfunction "2_P2") (pintype "passive"))
      (node (ref "JP2") (pin "3") (pinfunction "3_3") (pintype "passive"))
      (node (ref "JP2") (pin "4") (pinfunction "4_4") (pintype "passive"))
      (node (ref "JP2") (pin "5") (pinfunction "5_5") (pintype "passive"))
      (node (ref "JP2") (pin "6") (pinfunction "6_6") (pintype "passive"))
      (node (ref "JP2") (pin "7") (pinfunction "7_7") (pintype "passive"))
      (node (ref "JP2") (pin "8") (pinfunction "8_8") (pintype "passive"))
      (node (ref "JTAG") (pin "3") (pinfunction "3_3") (pintype "passive"))
      (node (ref "JTAG") (pin "5") (pinfunction "5_5") (pintype "passive"))
      (node (ref "JTAG") (pin "9") (pinfunction "9_9") (pintype "passive"))
      (node (ref "LED1") (pin "2") (pinfunction "C_2") (pintype "bidirectional"))
      (node (ref "LED2") (pin "2") (pinfunction "C_2") (pintype "bidirectional"))
      (node (ref "LED3") (pin "2") (pinfunction "C_2") (pintype "bidirectional"))
      (node (ref "Q2") (pin "E") (pinfunction "E_E") (pintype "passive"))
      (node (ref "Q3") (pin "E") (pinfunction "E_E") (pintype "passive"))
      (node (ref "Q4") (pin "E") (pinfunction "E_E") (pintype "passive"))
      (node (ref "Q5") (pin "E") (pinfunction "E_E") (pintype "passive"))
      (node (ref "Q6") (pin "E") (pinfunction "E_E") (pintype "passive"))
      (node (ref "R17") (pin "P$1") (pinfunction "E_P$1") (pintype "passive"))
      (node (ref "R18") (pin "P$1") (pinfunction "E_P$1") (pintype "passive"))
      (node (ref "R19") (pin "P$1") (pinfunction "E_P$1") (pintype "passive"))
      (node (ref "R26") (pin "1") (pinfunction "1_1") (pintype "passive"))
      (node (ref "R50") (pin "1") (pinfunction "1_1") (pintype "passive"))
      (node (ref "R52") (pin "1") (pinfunction "1_1") (pintype "passive"))
      (node (ref "R6") (pin "P$3") (pinfunction "A_P$3") (pintype "passive"))
      (node (ref "R8") (pin "1") (pinfunction "1_1") (pintype "passive"))
      (node (ref "SW3") (pin "1") (pinfunction "P_1") (pintype "passive"))
      (node (ref "SW3") (pin "2") (pinfunction "P1_2") (pintype "passive"))
      (node (ref "SW4") (pin "1") (pinfunction "P_1") (pintype "passive"))
      (node (ref "SW4") (pin "2") (pinfunction "P1_2") (pintype "passive"))
      (node (ref "UC1") (pin "20") (pinfunction "PB2/BOOT1_20") (pintype "bidirectional"))
      (node (ref "UC1") (pin "23") (pinfunction "VSS_1_23") (pintype "power_in"))
      (node (ref "UC1") (pin "35") (pinfunction "VSS_2_35") (pintype "power_in"))
      (node (ref "UC1") (pin "47") (pinfunction "VSS_3_47") (pintype "power_in"))
      (node (ref "UC1") (pin "8") (pinfunction "VSS_A_8") (pintype "power_in"))
    )
    (net (code "19") (name "JTCK") (class "Default")
      (node (ref "JTAG") (pin "4") (pinfunction "4_4") (pintype "passive"))
      (node (ref "UC1") (pin "37") (pinfunction "PA14/JTCK/SWCLK_37") (pintype "bidirectional"))
    )
    (net (code "20") (name "JTDI") (class "Default")
      (node (ref "JTAG") (pin "8") (pinfunction "8_8") (pintype "passive"))
      (node (ref "UC1") (pin "38") (pinfunction "PA15/JTDI_38") (pintype "bidirectional"))
    )
    (net (code "21") (name "JTDO") (class "Default")
      (node (ref "JTAG") (pin "6") (pinfunction "6_6") (pintype "passive"))
      (node (ref "UC1") (pin "39") (pinfunction "PB3/JTDO_39") (pintype "bidirectional"))
    )
    (net (code "22") (name "JTMS") (class "Default")
      (node (ref "JTAG") (pin "2") (pinfunction "2_2") (pintype "passive"))
      (node (ref "UC1") (pin "34") (pinfunction "PA13/JTMS/SWDIO_34") (pintype "bidirectional"))
    )
    (net (code "23") (name "LEVEL_ADC") (class "Default")
      (node (ref "C34") (pin "2") (pinfunction "2_2") (pintype "passive"))
      (node (ref "IC9") (pin "7") (pinfunction "OUT_7") (pintype "output"))
      (node (ref "R45") (pin "1") (pinfunction "1_1") (pintype "passive"))
      (node (ref "UC1") (pin "16") (pinfunction "PA6/SPI1_MISO/ADC12_IN6/TIM3_CH1_16") (pintype "bidirectional"))
    )
    (net (code "24") (name "Net-(C19-Pad1)") (class "Default")
      (node (ref "C19") (pin "1") (pinfunction "1_1") (pintype "passive"))
      (node (ref "R13") (pin "1") (pinfunction "1_1") (pintype "passive"))
      (node (ref "R15") (pin "2") (pinfunction "2_2") (pintype "passive"))
    )
    (net (code "25") (name "Net-(C21-Pad1)") (class "Default")
      (node (ref "C21") (pin "1") (pinfunction "1_1") (pintype "passive"))
      (node (ref "R14") (pin "1") (pinfunction "1_1") (pintype "passive"))
      (node (ref "R16") (pin "2") (pinfunction "2_2") (pintype "passive"))
    )
    (net (code "26") (name "Net-(G1-AC1)") (class "Default")
      (node (ref "G1") (pin "~1") (pinfunction "AC1_~1") (pintype "passive"))
      (node (ref "JP2") (pin "1") (pinfunction "1_1") (pintype "passive"))
      (node (ref "JP2") (pin "2") (pinfunction "2_2") (pintype "passive"))
    )
    (net (code "27") (name "Net-(G1-AC2)") (class "Default")
      (node (ref "G1") (pin "~2") (pinfunction "AC2_~2") (pintype "passive"))
      (node (ref "JP2") (pin "10") (pinfunction "10_10") (pintype "passive"))
      (node (ref "JP2") (pin "9") (pinfunction "9_9") (pintype "passive"))
    )
    (net (code "28") (name "Net-(IC5A--IN)") (class "Default")
      (node (ref "IC5") (pin "2") (pinfunction "-IN_2") (pintype "input"))
      (node (ref "R20") (pin "1") (pinfunction "1_1") (pintype "passive"))
      (node (ref "R21") (pin "1") (pinfunction "1_1") (pintype "passive"))
      (node (ref "R23") (pin "2") (pinfunction "2_2") (pintype "passive"))
    )
    (net (code "29") (name "Net-(IC5A-OUT)") (class "Default")
      (node (ref "IC5") (pin "1") (pinfunction "OUT_1") (pintype "output"))
      (node (ref "R22") (pin "2") (pinfunction "2_2") (pintype "passive"))
      (node (ref "R23") (pin "1") (pinfunction "1_1") (pintype "passive"))
    )
    (net (code "30") (name "Net-(IC5B-+IN)") (class "Default")
      (node (ref "C22") (pin "1") (pinfunction "1_1") (pintype "passive"))
      (node (ref "IC5") (pin "5") (pinfunction "+IN_5") (pintype "input"))
      (node (ref "R15") (pin "1") (pinfunction "1_1") (pintype "passive"))
    )
    (net (code "31") (name "Net-(IC5B--IN)") (class "Default")
      (node (ref "C19") (pin "2") (pinfunction "2_2") (pintype "passive"))
      (node (ref "IC5") (pin "6") (pinfunction "-IN_6") (pintype "input"))
      (node (ref "IC5") (pin "7") (pinfunction "OUT_7") (pintype "output"))
      (node (ref "R20") (pin "2") (pinfunction "2_2") (pintype "passive"))
    )
    (net (code "32") (name "Net-(IC6A-+IN)") (class "Default")
      (node (ref "C21") (pin "2") (pinfunction "2_2") (pintype "passive"))
      (node (ref "IC6") (pin "3") (pinfunction "+IN_3") (pintype "input"))
      (node (ref "IC6") (pin "6") (pinfunction "-IN_6") (pintype "input"))
      (node (ref "IC6") (pin "7") (pinfunction "OUT_7") (pintype "output"))
    )
    (net (code "33") (name "Net-(IC6A--IN)") (class "Default")
      (node (ref "IC6") (pin "2") (pinfunction "-IN_2") (pintype "input"))
      (node (ref "R25") (pin "2") (pinfunction "2_2") (pintype "passive"))
      (node (ref "R26") (pin "2") (pinfunction "2_2") (pintype "passive"))
    )
    (net (code "34") (name "Net-(IC6A-OUT)") (class "Default")
      (node (ref "IC6") (pin "1") (pinfunction "OUT_1") (pintype "output"))
      (node (ref "R24") (pin "2") (pinfunction "2_2") (pintype "passive"))
      (node (ref "R25") (pin "1") (pinfunction "1_1") (pintype "passive"))
    )
    (net (code "35") (name "Net-(IC6B-+IN)") (class "Default")
      (node (ref "C23") (pin "1") (pinfunction "1_1") (pintype "passive"))
      (node (ref "IC6") (pin "5") (pinfunction "+IN_5") (pintype "input"))
      (node (ref "R16") (pin "1") (pinfunction "1_1") (pintype "passive"))
    )
    (net (code "36") (name "Net-(IC8A--IN)") (class "Default")
      (node (ref "C31") (pin "1") (pinfunction "1_1") (pintype "passive"))
      (node (ref "IC8") (pin "2") (pinfunction "-IN_2") (pintype "input"))
      (node (ref "R37") (pin "2") (pinfunction "2_2") (pintype "passive"))
      (node (ref "R38") (pin "1") (pinfunction "1_1") (pintype "passive"))
      (node (ref "R39") (pin "1") (pinfunction "1_1") (pintype "passive"))
    )
    (net (code "37") (name "Net-(IC8B--IN)") (class "Default")
      (node (ref "C27") (pin "1") (pinfunction "1_1") (pintype "passive"))
      (node (ref "IC8") (pin "6") (pinfunction "-IN_6") (pintype "input"))
      (node (ref "R34") (pin "2") (pinfunction "2_2") (pintype "passive"))
      (node (ref "R35") (pin "1") (pinfunction "1_1") (pintype "passive"))
      (node (ref "R36") (pin "1") (pinfunction "1_1") (pintype "passive"))
    )
    (net (code "38") (name "Net-(IC9A--IN)") (class "Default")
      (node (ref "C32") (pin "1") (pinfunction "1_1") (pintype "passive"))
      (node (ref "IC9") (pin "2") (pinfunction "-IN_2") (pintype "input"))
      (node (ref "R40") (pin "2") (pinfunction "2_2") (pintype "passive"))
      (node (ref "R41") (pin "1") (pinfunction "1_1") (pintype "passive"))
      (node (ref "R42") (pin "1") (pinfunction "1_1") (pintype "passive"))
    )
    (net (code "39") (name "Net-(IC9B--IN)") (class "Default")
      (node (ref "C34") (pin "1") (pinfunction "1_1") (pintype "passive"))
      (node (ref "IC9") (pin "6") (pinfunction "-IN_6") (pintype "input"))
      (node (ref "R43") (pin "1") (pinfunction "1_1") (pintype "passive"))
      (node (ref "R44") (pin "1") (pinfunction "1_1") (pintype "passive"))
      (node (ref "R45") (pin "2") (pinfunction "2_2") (pintype "passive"))
    )
    (net (code "40") (name "Net-(IC9C--IN)") (class "Default")
      (node (ref "C28") (pin "1") (pinfunction "1_1") (pintype "passive"))
      (node (ref "IC9") (pin "9") (pinfunction "-IN_9") (pintype "input"))
      (node (ref "R31") (pin "1") (pinfunction "1_1") (pintype "passive"))
      (node (ref "R32") (pin "1") (pinfunction "1_1") (pintype "passive"))
      (node (ref "R33") (pin "2") (pinfunction "2_2") (pintype "passive"))
    )
    (net (code "41") (name "Net-(IC9D--IN)") (class "Default")
      (node (ref "C29") (pin "1") (pinfunction "1_1") (pintype "passive"))
      (node (ref "IC9") (pin "13") (pinfunction "-IN_13") (pintype "input"))
      (node (ref "R28") (pin "2") (pinfunction "2_2") (pintype "passive"))
      (node (ref "R29") (pin "1") (pinfunction "1_1") (pintype "passive"))
      (node (ref "R30") (pin "1") (pinfunction "1_1") (pintype "passive"))
    )
    (net (code "42") (name "Net-(J1-3)") (class "Default")
      (node (ref "J1") (pin "P3") (pinfunction "3_P3") (pintype "passive"))
      (node (ref "R42") (pin "2") (pinfunction "2_2") (pintype "passive"))
    )
    (net (code "43") (name "Net-(J2-3)") (class "Default")
      (node (ref "J2") (pin "P3") (pinfunction "3_P3") (pintype "passive"))
      (node (ref "R29") (pin "2") (pinfunction "2_2") (pintype "passive"))
    )
    (net (code "44") (name "Net-(J3-3)") (class "Default")
      (node (ref "J3") (pin "P3") (pinfunction "3_P3") (pintype "passive"))
      (node (ref "R32") (pin "2") (pinfunction "2_2") (pintype "passive"))
    )
    (net (code "45") (name "Net-(J4-3)") (class "Default")
      (node (ref "J4") (pin "P3") (pinfunction "3_P3") (pintype "passive"))
      (node (ref "R55") (pin "1") (pinfunction "1_1") (pintype "passive"))
    )
    (net (code "46") (name "Net-(J5-3)") (class "Default")
      (node (ref "J5") (pin "P3") (pinfunction "3_P3") (pintype "passive"))
      (node (ref "R56") (pin "1") (pinfunction "1_1") (pintype "passive"))
    )
    (net (code "47") (name "Net-(J6-3)") (class "Default")
      (node (ref "J6") (pin "P3") (pinfunction "3_P3") (pintype "passive"))
      (node (ref "R39") (pin "2") (pinfunction "2_2") (pintype "passive"))
    )
    (net (code "48") (name "Net-(J7-2)") (class "Default")
      (node (ref "J7") (pin "P2") (pinfunction "2_P2") (pintype "passive"))
      (node (ref "R46") (pin "1") (pinfunction "1_1") (pintype "passive"))
    )
    (net (code "49") (name "Net-(J7-3)") (class "Default")
      (node (ref "J7") (pin "P3") (pinfunction "3_P3") (pintype "passive"))
      (node (ref "R36") (pin "2") (pinfunction "2_2") (pintype "passive"))
    )
    (net (code "50") (name "Net-(J8-2)") (class "Default")
      (node (ref "J8") (pin "P2") (pinfunction "2_P2") (pintype "passive"))
      (node (ref "R60") (pin "2") (pinfunction "2_2") (pintype "passive"))
    )
    (net (code "51") (name "Net-(J8-3)") (class "Default")
      (node (ref "J8") (pin "P3") (pinfunction "3_P3") (pintype "passive"))
      (node (ref "R44") (pin "2") (pinfunction "2_2") (pintype "passive"))
    )
    (net (code "52") (name "Net-(J9-3)") (class "Default")
      (node (ref "J9") (pin "P3") (pinfunction "3_P3") (pintype "passive"))
      (node (ref "R54") (pin "1") (pinfunction "1_1") (pintype "passive"))
    )
    (net (code "53") (name "Net-(J10-3)") (class "Default")
      (node (ref "J10") (pin "P3") (pinfunction "3_P3") (pintype "passive"))
      (node (ref "Q5") (pin "C") (pinfunction "C_C") (pintype "passive"))
      (node (ref "R50") (pin "2") (pinfunction "2_2") (pintype "passive"))
      (node (ref "R51") (pin "1") (pinfunction "1_1") (pintype "passive"))
    )
    (net (code "54") (name "Net-(J11-3)") (class "Default")
      (node (ref "J11") (pin "P3") (pinfunction "3_P3") (pintype "passive"))
      (node (ref "Q6") (pin "C") (pinfunction "C_C") (pintype "passive"))
      (node (ref "R52") (pin "2") (pinfunction "2_2") (pintype "passive"))
      (node (ref "R53") (pin "1") (pinfunction "1_1") (pintype "passive"))
    )
    (net (code "55") (name "Net-(J12-3)") (class "Default")
      (node (ref "J12") (pin "P3") (pinfunction "3_P3") (pintype "passive"))
      (node (ref "R24") (pin "1") (pinfunction "1_1") (pintype "passive"))
    )
    (net (code "56") (name "Net-(J13-3)") (class "Default")
      (node (ref "J13") (pin "P3") (pinfunction "3_P3") (pintype "passive"))
      (node (ref "R22") (pin "1") (pinfunction "1_1") (pintype "passive"))
    )
    (net (code "57") (name "Net-(LED1-GRN)") (class "Default")
      (node (ref "LED1") (pin "1") (pinfunction "GRN_1") (pintype "bidirectional"))
      (node (ref "R2") (pin "2") (pinfunction "2_2") (pintype "passive"))
    )
    (net (code "58") (name "Net-(LED1-RED)") (class "Default")
      (node (ref "LED1") (pin "3") (pinfunction "RED_3") (pintype "bidirectional"))
      (node (ref "R3") (pin "2") (pinfunction "2_2") (pintype "passive"))
    )
    (net (code "59") (name "Net-(LED2-GRN)") (class "Default")
      (node (ref "LED2") (pin "1") (pinfunction "GRN_1") (pintype "bidirectional"))
      (node (ref "R4") (pin "2") (pinfunction "2_2") (pintype "passive"))
    )
    (net (code "60") (name "Net-(LED2-RED)") (class "Default")
      (node (ref "LED2") (pin "3") (pinfunction "RED_3") (pintype "bidirectional"))
      (node (ref "R7") (pin "2") (pinfunction "2_2") (pintype "passive"))
    )
    (net (code "61") (name "Net-(LED3-GRN)") (class "Default")
      (node (ref "LED3") (pin "1") (pinfunction "GRN_1") (pintype "bidirectional"))
      (node (ref "R9") (pin "2") (pinfunction "2_2") (pintype "passive"))
    )
    (net (code "62") (name "Net-(LED3-RED)") (class "Default")
      (node (ref "LED3") (pin "3") (pinfunction "RED_3") (pintype "bidirectional"))
      (node (ref "R10") (pin "2") (pinfunction "2_2") (pintype "passive"))
    )
    (net (code "63") (name "Net-(Q2-PadB)") (class "Default")
      (node (ref "Q2") (pin "B") (pinfunction "B_B") (pintype "passive"))
      (node (ref "R55") (pin "2") (pinfunction "2_2") (pintype "passive"))
    )
    (net (code "64") (name "Net-(Q3-PadB)") (class "Default")
      (node (ref "Q3") (pin "B") (pinfunction "B_B") (pintype "passive"))
      (node (ref "R54") (pin "2") (pinfunction "2_2") (pintype "passive"))
    )
    (net (code "65") (name "Net-(Q4-PadB)") (class "Default")
      (node (ref "Q4") (pin "B") (pinfunction "B_B") (pintype "passive"))
      (node (ref "R56") (pin "2") (pinfunction "2_2") (pintype "passive"))
    )
    (net (code "66") (name "Net-(Q5-PadB)") (class "Default")
      (node (ref "Q5") (pin "B") (pinfunction "B_B") (pintype "passive"))
      (node (ref "R57") (pin "2") (pinfunction "2_2") (pintype "passive"))
    )
    (net (code "67") (name "Net-(Q6-PadB)") (class "Default")
      (node (ref "Q6") (pin "B") (pinfunction "B_B") (pintype "passive"))
      (node (ref "R58") (pin "2") (pinfunction "2_2") (pintype "passive"))
    )
    (net (code "68") (name "Net-(R5-E)") (class "Default")
      (node (ref "R5") (pin "P$1") (pinfunction "E_P$1") (pintype "passive"))
      (node (ref "R8") (pin "2") (pinfunction "2_2") (pintype "passive"))
    )
    (net (code "69") (name "Net-(R5-S)") (class "Default")
      (node (ref "R38") (pin "2") (pinfunction "2_2") (pintype "passive"))
      (node (ref "R5") (pin "P$2") (pinfunction "S_P$2") (pintype "passive"))
    )
    (net (code "70") (name "Net-(R17-S)") (class "Default")
      (node (ref "R17") (pin "P$2") (pinfunction "S_P$2") (pintype "passive"))
      (node (ref "R41") (pin "2") (pinfunction "2_2") (pintype "passive"))
    )
    (net (code "71") (name "Net-(R18-S)") (class "Default")
      (node (ref "R18") (pin "P$2") (pinfunction "S_P$2") (pintype "passive"))
      (node (ref "R30") (pin "2") (pinfunction "2_2") (pintype "passive"))
    )
    (net (code "72") (name "Net-(R19-S)") (class "Default")
      (node (ref "R19") (pin "P$2") (pinfunction "S_P$2") (pintype "passive"))
      (node (ref "R31") (pin "2") (pinfunction "2_2") (pintype "passive"))
    )
    (net (code "73") (name "Net-(R59-A)") (class "Default")
      (node (ref "R21") (pin "2") (pinfunction "2_2") (pintype "passive"))
      (node (ref "R59") (pin "1") (pinfunction "A_1") (pintype "passive"))
    )
    (net (code "74") (name "Net-(UC1-PB4{slash}NJTRST)") (class "Default")
      (node (ref "R2") (pin "1") (pinfunction "1_1") (pintype "passive"))
      (node (ref "UC1") (pin "40") (pinfunction "PB4/NJTRST_40") (pintype "bidirectional"))
    )
    (net (code "75") (name "Net-(UC1-PB5{slash}I2C1_SMBA)") (class "Default")
      (node (ref "R3") (pin "1") (pinfunction "1_1") (pintype "passive"))
      (node (ref "UC1") (pin "41") (pinfunction "PB5/I2C1_SMBA_41") (pintype "input"))
    )
    (net (code "76") (name "Net-(UC1-PB6{slash}I2C1_SCL{slash}TIM4_CH1)") (class "Default")
      (node (ref "R4") (pin "1") (pinfunction "1_1") (pintype "passive"))
      (node (ref "UC1") (pin "42") (pinfunction "PB6/I2C1_SCL/TIM4_CH1_42") (pintype "input"))
    )
    (net (code "77") (name "Net-(UC1-PB7{slash}I2C1_SDA{slash}TIM4_CH2)") (class "Default")
      (node (ref "R7") (pin "1") (pinfunction "1_1") (pintype "passive"))
      (node (ref "UC1") (pin "43") (pinfunction "PB7/I2C1_SDA/TIM4_CH2_43") (pintype "bidirectional"))
    )
    (net (code "78") (name "Net-(UC1-PB8{slash}TIM4_CH3)") (class "Default")
      (node (ref "R9") (pin "1") (pinfunction "1_1") (pintype "passive"))
      (node (ref "UC1") (pin "45") (pinfunction "PB8/TIM4_CH3_45") (pintype "bidirectional"))
    )
    (net (code "79") (name "Net-(UC1-PB9{slash}TIM4_CH4)") (class "Default")
      (node (ref "R10") (pin "1") (pinfunction "1_1") (pintype "passive"))
      (node (ref "UC1") (pin "46") (pinfunction "PB9/TIM4_CH4_46") (pintype "input"))
    )
    (net (code "80") (name "Net-(UC1-PD0-OSC_IN)") (class "Default")
      (node (ref "C2") (pin "2") (pinfunction "2_2") (pintype "passive"))
      (node (ref "UC1") (pin "5") (pinfunction "PD0-OSC_IN_5") (pintype "input"))
      (node (ref "X1") (pin "P$2") (pinfunction "P$2_P$2") (pintype "bidirectional"))
    )
    (net (code "81") (name "Net-(UC1-PD1-OSC_OUT)") (class "Default")
      (node (ref "C17") (pin "2") (pinfunction "2_2") (pintype "passive"))
      (node (ref "UC1") (pin "6") (pinfunction "PD1-OSC_OUT_6") (pintype "input"))
      (node (ref "X1") (pin "P$1") (pinfunction "P$1_P$1") (pintype "bidirectional"))
    )
    (net (code "82") (name "PROC_ADC") (class "Default")
      (node (ref "C28") (pin "2") (pinfunction "2_2") (pintype "passive"))
      (node (ref "IC9") (pin "8") (pinfunction "OUT_8") (pintype "output"))
      (node (ref "R33") (pin "1") (pinfunction "1_1") (pintype "passive"))
      (node (ref "UC1") (pin "17") (pinfunction "PA7/SPI1_MOSI/ADC12_IN7/TIM3_CH2_17") (pintype "bidirectional"))
    )
    (net (code "83") (name "RANGE_SW") (class "Default")
      (node (ref "SW4") (pin "3") (pinfunction "S_3") (pintype "passive"))
      (node (ref "SW4") (pin "4") (pinfunction "S1_4") (pintype "passive"))
      (node (ref "UC1") (pin "11") (pinfunction "PA1/USART2_RTS/ADC12_IN1/TIM2_CH2_11") (pintype "bidirectional"))
    )
    (net (code "84") (name "RESET") (class "Default")
      (node (ref "JTAG") (pin "10") (pinfunction "10_10") (pintype "passive"))
      (node (ref "UC1") (pin "7") (pinfunction "NRST_7") (pintype "input"))
    )
    (net (code "85") (name "RX") (class "Default")
      (node (ref "UC1") (pin "31") (pinfunction "PA10/USART1_RX/TIM1_CH3_31") (pintype "bidirectional"))
    )
    (net (code "86") (name "SHAPE_ADC") (class "Default")
      (node (ref "C32") (pin "2") (pinfunction "2_2") (pintype "passive"))
      (node (ref "IC9") (pin "1") (pinfunction "OUT_1") (pintype "output"))
      (node (ref "R40") (pin "1") (pinfunction "1_1") (pintype "passive"))
      (node (ref "UC1") (pin "15") (pinfunction "PA5/SPI1_SCK/ADC12_IN5_15") (pintype "bidirectional"))
    )
    (net (code "87") (name "START") (class "Default")
      (node (ref "Q2") (pin "C") (pinfunction "C_C") (pintype "passive"))
      (node (ref "R47") (pin "1") (pinfunction "1_1") (pintype "passive"))
      (node (ref "UC1") (pin "22") (pinfunction "PB11/I2C2_SDA/USART3_RX_22") (pintype "input"))
    )
    (net (code "88") (name "TX") (class "Default")
      (node (ref "UC1") (pin "30") (pinfunction "PA9/USART1_TX/TIM1_CH2_30") (pintype "input"))
    )
    (net (code "89") (name "UNI") (class "Default")
      (node (ref "IC4") (pin "4") (pinfunction "OUTA_4") (pintype "output"))
      (node (ref "R14") (pin "2") (pinfunction "2_2") (pintype "passive"))
    )
    (net (code "90") (name "VCC") (class "Default")
      (node (ref "C18") (pin "1") (pinfunction "1_1") (pintype "passive"))
      (node (ref "C20") (pin "1") (pinfunction "1_1") (pintype "passive"))
      (node (ref "C3") (pin "+") (pinfunction "+_+") (pintype "passive"))
      (node (ref "C8") (pin "+") (pinfunction "+_+") (pintype "passive"))
      (node (ref "G1") (pin "+") (pinfunction "+_+") (pintype "passive"))
      (node (ref "IC1") (pin "3") (pinfunction "VIN_3") (pintype "input"))
      (node (ref "IC3") (pin "3") (pinfunction "VIN_3") (pintype "input"))
      (node (ref "IC5") (pin "8") (pinfunction "V+_8") (pintype "power_in"))
      (node (ref "IC6") (pin "8") (pinfunction "V+_8") (pintype "power_in"))
      (node (ref "R51") (pin "2") (pinfunction "2_2") (pintype "passive"))
      (node (ref "R53") (pin "2") (pinfunction "2_2") (pintype "passive"))
      (node (ref "R60") (pin "1") (pinfunction "1_1") (pintype "passive"))
    )
    (net (code "91") (name "VEE") (class "Default")
      (node (ref "C10") (pin "-") (pinfunction "-_-") (pintype "passive"))
      (node (ref "C24") (pin "2") (pinfunction "2_2") (pintype "passive"))
      (node (ref "C25") (pin "2") (pinfunction "2_2") (pintype "passive"))
      (node (ref "G1") (pin "-") (pinfunction "-_-") (pintype "passive"))
      (node (ref "IC5") (pin "4") (pinfunction "V-_4") (pintype "power_in"))
      (node (ref "IC6") (pin "4") (pinfunction "V-_4") (pintype "power_in"))
      (node (ref "R27") (pin "1") (pinfunction "1_1") (pintype "passive"))
    )
    (net (code "92") (name "VOCT_ADC") (class "Default")
      (node (ref "C31") (pin "2") (pinfunction "2_2") (pintype "passive"))
      (node (ref "IC8") (pin "1") (pinfunction "OUT_1") (pintype "output"))
      (node (ref "R37") (pin "1") (pinfunction "1_1") (pintype "passive"))
      (node (ref "UC1") (pin "13") (pinfunction "PA3/USART2_RX/ADC12_IN3/TIM2_CH4_13") (pintype "bidirectional"))
    )
    (net (code "93") (name "unconnected-(J1-2-PadP2)") (class "Default")
      (node (ref "J1") (pin "P2") (pinfunction "2_P2") (pintype "passive"))
    )
    (net (code "94") (name "unconnected-(J2-2-PadP2)") (class "Default")
      (node (ref "J2") (pin "P2") (pinfunction "2_P2") (pintype "passive"))
    )
    (net (code "95") (name "unconnected-(J3-2-PadP2)") (class "Default")
      (node (ref "J3") (pin "P2") (pinfunction "2_P2") (pintype "passive"))
    )
    (net (code "96") (name "unconnected-(J6-2-PadP2)") (class "Default")
      (node (ref "J6") (pin "P2") (pinfunction "2_P2") (pintype "passive"))
    )
    (net (code "97") (name "unconnected-(J10-2-PadP2)") (class "Default")
      (node (ref "J10") (pin "P2") (pinfunction "2_P2") (pintype "passive"))
    )
    (net (code "98") (name "unconnected-(J11-2-PadP2)") (class "Default")
      (node (ref "J11") (pin "P2") (pinfunction "2_P2") (pintype "passive"))
    )
    (net (code "99") (name "unconnected-(J12-2-PadP2)") (class "Default")
      (node (ref "J12") (pin "P2") (pinfunction "2_P2") (pintype "passive"))
    )
    (net (code "100") (name "unconnected-(J13-2-PadP2)") (class "Default")
      (node (ref "J13") (pin "P2") (pinfunction "2_P2") (pintype "passive"))
    )
    (net (code "101") (name "unconnected-(JTAG-Pad7)") (class "Default")
      (node (ref "JTAG") (pin "7") (pinfunction "7_7") (pintype "passive"))
    )
    (net (code "102") (name "unconnected-(UC1-PA8{slash}USART1_CK{slash}TIM1_CH1{slash}MCO-Pad29)") (class "Default")
      (node (ref "UC1") (pin "29") (pinfunction "PA8/USART1_CK/TIM1_CH1/MCO_29") (pintype "bidirectional"))
    )
    (net (code "103") (name "unconnected-(UC1-PB14{slash}SPI2_MISO{slash}USART3_RTS{slash}TIM1_CH2N-Pad27)") (class "Default")
      (node (ref "UC1") (pin "27") (pinfunction "PB14/SPI2_MISO/USART3_RTS/TIM1_CH2N_27") (pintype "input"))
    )
    (net (code "104") (name "unconnected-(UC1-PC13-TAMPER-RTC-Pad2)") (class "Default")
      (node (ref "UC1") (pin "2") (pinfunction "PC13-TAMPER-RTC_2") (pintype "input"))
    )
    (net (code "105") (name "unconnected-(UC1-PC14-OSC32_IN-Pad3)") (class "Default")
      (node (ref "UC1") (pin "3") (pinfunction "PC14-OSC32_IN_3") (pintype "input"))
    )
    (net (code "106") (name "unconnected-(UC1-PC15-OSC32_OUT-Pad4)") (class "Default")
      (node (ref "UC1") (pin "4") (pinfunction "PC15-OSC32_OUT_4") (pintype "input"))
    )
  )
)
